# Topsheet.net
KiCad netlist of a schematic drawn in Altium Designer
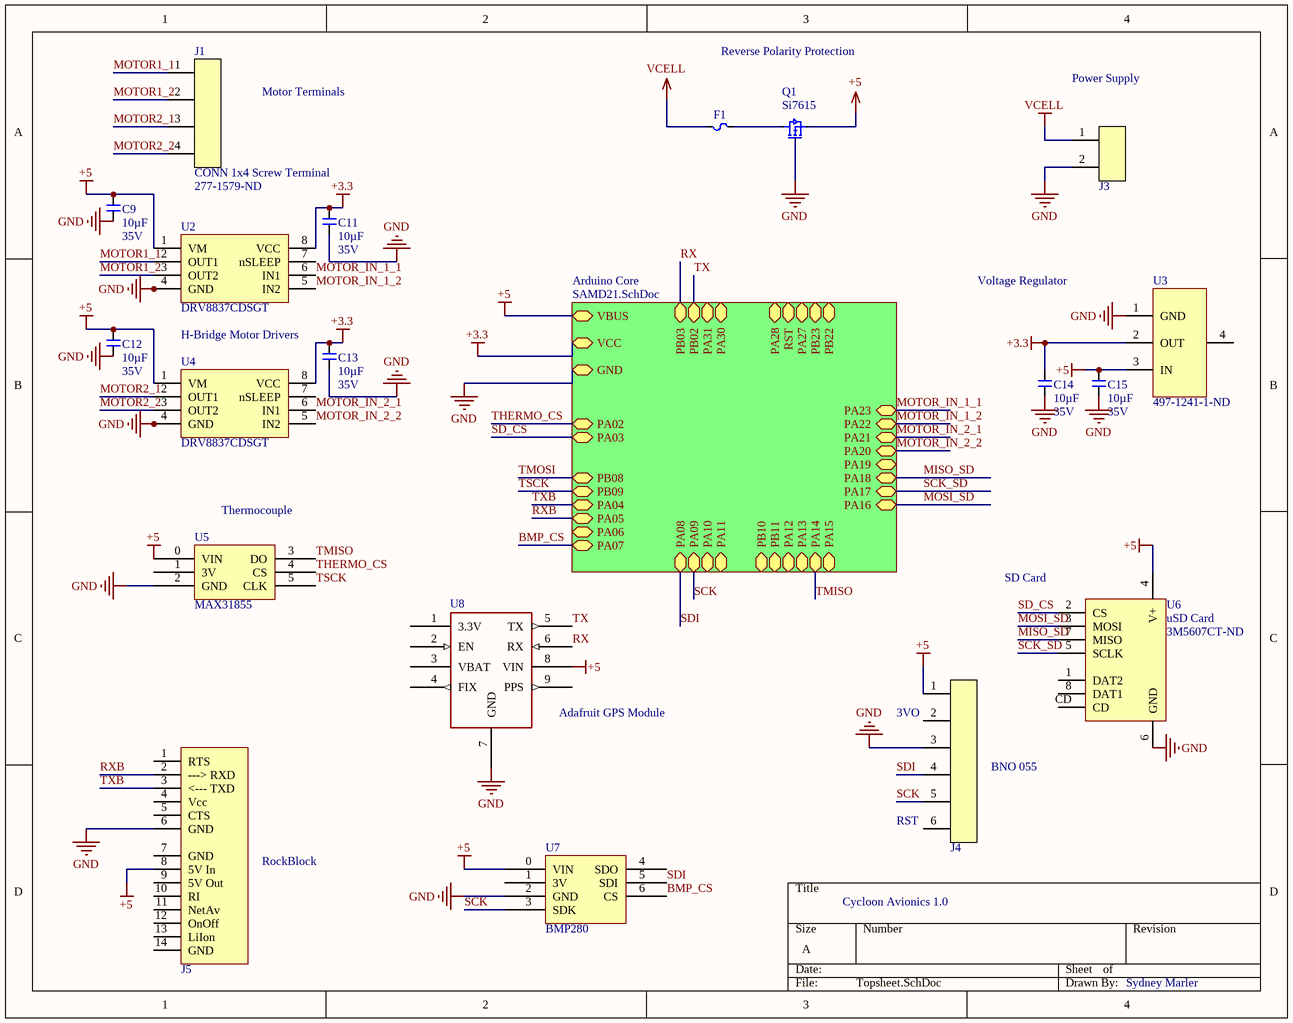
[diagram p0: Topsheet.SchDoc]

(export (version "E")
  (design (tool "Eeschema 10.0.6"))
  (components
    (comp (ref "C9")
      (value "__template_cap")
      (footprint "C0603")
      (description "CAP CER 10UF 35V X5R 0603 20%")
      (fields
        (field (name "CAPACITANCE (SHORTHAND)") "10µF")
        (field (name "RATED VOLTAGE") "35V")
        (field (name "MANUFACTURER") "Murata Electronics North America")
      )
      (libsource (lib "passives") (part "__template_cap"))
    )
    (comp (ref "C11")
      (value "__template_cap")
      (footprint "C0603")
      (description "CAP CER 10UF 35V X5R 0603 20%")
      (fields
        (field (name "CAPACITANCE (SHORTHAND)") "10µF")
        (field (name "RATED VOLTAGE") "35V")
        (field (name "MANUFACTURER") "Murata Electronics North America")
      )
      (libsource (lib "passives") (part "__template_cap"))
    )
    (comp (ref "C12")
      (value "__template_cap")
      (footprint "C0603")
      (description "CAP CER 10UF 35V X5R 0603 20%")
      (fields
        (field (name "CAPACITANCE (SHORTHAND)") "10µF")
        (field (name "RATED VOLTAGE") "35V")
        (field (name "MANUFACTURER") "Murata Electronics North America")
      )
      (libsource (lib "passives") (part "__template_cap"))
    )
    (comp (ref "C13")
      (value "__template_cap")
      (footprint "C0603")
      (description "CAP CER 10UF 35V X5R 0603 20%")
      (fields
        (field (name "CAPACITANCE (SHORTHAND)") "10µF")
        (field (name "RATED VOLTAGE") "35V")
        (field (name "MANUFACTURER") "Murata Electronics North America")
      )
      (libsource (lib "passives") (part "__template_cap"))
    )
    (comp (ref "C14")
      (value "__template_cap")
      (footprint "C0603")
      (description "CAP CER 10UF 35V X5R 0603 20%")
      (fields
        (field (name "CAPACITANCE (SHORTHAND)") "10µF")
        (field (name "RATED VOLTAGE") "35V")
        (field (name "MANUFACTURER") "Murata Electronics North America")
      )
      (libsource (lib "passives") (part "__template_cap"))
    )
    (comp (ref "C15")
      (value "__template_cap")
      (footprint "C0603")
      (description "CAP CER 10UF 35V X5R 0603 20%")
      (fields
        (field (name "CAPACITANCE (SHORTHAND)") "10µF")
        (field (name "RATED VOLTAGE") "35V")
        (field (name "MANUFACTURER") "Murata Electronics North America")
      )
      (libsource (lib "passives") (part "__template_cap"))
    )
    (comp (ref "F1") (value "__template_fuse") (libsource (lib "SSI") (part "__template_fuse")))
    (comp (ref "J1")
      (value "CONN 1x4 Screw Terminal")
      (footprint "CONN_1x4_5mm")
      (description "CONN 1x4 Screw Terminal: Phoenix Contact 1935187")
      (fields (field (name "SUPPLIER PART NUMBER 1") "277-1579-ND"))
      (libsource (lib "SSI") (part "CONN_1x4_PhoenixContact_1935187"))
    )
    (comp (ref "J3")
      (value "CONN HEADER 2POS VERT T/H")
      (footprint "CONN_1x2_100MIL")
      (fields (field (name "MANUFACTURER") "FCI") (field (name "MANUFACTURER PART NUMBER") "77311-118-02LF"))
      (libsource (lib "SSI") (part "CONN_1x2"))
    )
    (comp (ref "J4")
      (value "CONN HEADER 6POS T/H")
      (footprint "CONN_1x6_100MIL")
      (libsource (lib "SSI") (part "CONN_1x6"))
    )
    (comp (ref "J5")
      (value "ROCKBLOCK_V2")
      (footprint "ROCKBLOCK_V2")
      (description "CHILD OF SATAN, SOURCE OF BOTH TREMENDOUS FORTUNE AND UNSPEAKABLE ANGUISH")
      (libsource (lib "SSI") (part "ROCKBLOCK_V2"))
    )
    (comp (ref "Q1")
      (value "Si7615")
      (footprint "POWERPAK_1212-8_SINGLE")
      (description "MOSFET P-CH 20V 35A PPK")
      (fields
        (field (name "MANUFACTURER") "Vishay Siliconix")
        (field (name "MANUFACTURER PART NUMBER") "SI7615ADN-T1-GE3")
      )
      (libsource (lib "SSI") (part "PFET_SI7615ADN-T1"))
    )
    (comp (ref "U2")
      (value "DRV8837CDSGT")
      (footprint "8WSON")
      (description "MOTOR DRIVER 1A")
      (fields (field (name "MANUFACTURER") "Texas Instruments"))
      (libsource (lib "SSI") (part "MOTOR_HBRIDGE_DRV8837C"))
    )
    (comp (ref "U3")
      (value "LDO_LD1117S33CTR")
      (footprint "4SOT223")
      (description "IC VOLTAGE REG 3.3V 800MA SOT223 INDUSTRIAL TEMP")
      (fields
        (field (name "MANUFACTURER") "STMicroelectronics")
        (field (name "MANUFACTURER PART NUMBER") "LD1117S33CTR")
        (field (name "SUPPLIER PART NUMBER 1") "497-1241-1-ND")
      )
      (libsource (lib "SSI") (part "LDO_LD1117S33CTR"))
    )
    (comp (ref "U4")
      (value "DRV8837CDSGT")
      (footprint "8WSON")
      (description "MOTOR DRIVER 1A")
      (fields (field (name "MANUFACTURER") "Texas Instruments"))
      (libsource (lib "SSI") (part "MOTOR_HBRIDGE_DRV8837C"))
    )
    (comp (ref "U5")
      (value "MAX31855")
      (footprint "ADAFRUIT_THERMOCOUPLE_BREAKOUT")
      (libsource (lib "SSI") (part "ADAFRUIT_THERMOCOUPLE_BREAKOUT"))
    )
    (comp (ref "U6")
      (value "uSD Card")
      (footprint "MICROSD_CARD_SOCKET")
      (description "MICROSD CARD HOLDER, PUSH-PUSH")
      (fields
        (field (name "MANUFACTURER") "3M")
        (field (name "MANUFACTURER PART NUMBER") "2908-05WB-MG")
        (field (name "SUPPLIER PART NUMBER 1") "3M5607CT-ND")
      )
      (libsource (lib "SSI") (part "MICRO_SD_CARD_HOLDER"))
    )
    (comp (ref "U7")
      (value "BMP280")
      (footprint "ADAFRUIT_BMP280_BREAKOUT")
      (libsource (lib "SSI") (part "ADAFRUIT_BMP280_BREAKOUT"))
    )
    (comp (ref "U8")
      (value "Adafruit GPS Module")
      (footprint "adafruit_gps_746")
      (description "https://www.adafruit.com/product/746")
      (libsource (lib "modules") (part "ADAFRUIT_GPS_746"))
    )
  )
  (nets
    (net (code "1") (name "+3.3") (class "Default")
      (node (ref "C11") (pin "1") (pintype "passive"))
      (node (ref "C13") (pin "1") (pintype "passive"))
      (node (ref "C14") (pin "1") (pintype "passive"))
      (node (ref "U2") (pin "8") (pinfunction "VCC_8") (pintype "passive"))
      (node (ref "U3") (pin "2") (pinfunction "OUT_2") (pintype "passive"))
      (node (ref "U4") (pin "8") (pinfunction "VCC_8") (pintype "passive"))
    )
    (net (code "2") (name "+5") (class "Default")
      (node (ref "C12") (pin "1") (pintype "passive"))
      (node (ref "C15") (pin "1") (pintype "passive"))
      (node (ref "C9") (pin "1") (pintype "passive"))
      (node (ref "J4") (pin "1") (pinfunction "1_1") (pintype "passive"))
      (node (ref "J5") (pin "8") (pinfunction "5V_In_8") (pintype "passive"))
      (node (ref "Q1") (pin "2") (pintype "passive"))
      (node (ref "U2") (pin "1") (pinfunction "VM_1") (pintype "passive"))
      (node (ref "U3") (pin "3") (pinfunction "IN_3") (pintype "passive"))
      (node (ref "U4") (pin "1") (pinfunction "VM_1") (pintype "passive"))
      (node (ref "U5") (pin "0") (pinfunction "VIN_0") (pintype "passive"))
      (node (ref "U6") (pin "4") (pinfunction "V+_4") (pintype "passive"))
      (node (ref "U7") (pin "0") (pinfunction "VIN_0") (pintype "passive"))
      (node (ref "U8") (pin "8") (pinfunction "VIN_8") (pintype "power_in"))
    )
    (net (code "3") (name "/BMP_CS") (class "Default")
      (node (ref "U7") (pin "6") (pinfunction "CS_6") (pintype "passive"))
    )
    (net (code "4") (name "/MISO_SD") (class "Default")
      (node (ref "U6") (pin "7") (pinfunction "MISO_7") (pintype "passive"))
    )
    (net (code "5") (name "/MOSI_SD") (class "Default")
      (node (ref "U6") (pin "3") (pinfunction "MOSI_3") (pintype "passive"))
    )
    (net (code "6") (name "/MOTOR1_1") (class "Default")
      (node (ref "J1") (pin "1") (pinfunction "1_1") (pintype "passive"))
      (node (ref "U2") (pin "2") (pinfunction "OUT1_2") (pintype "passive"))
    )
    (net (code "7") (name "/MOTOR1_2") (class "Default")
      (node (ref "J1") (pin "2") (pinfunction "2_2") (pintype "passive"))
      (node (ref "U2") (pin "3") (pinfunction "OUT2_3") (pintype "passive"))
    )
    (net (code "8") (name "/MOTOR2_1") (class "Default")
      (node (ref "J1") (pin "3") (pinfunction "3_3") (pintype "passive"))
      (node (ref "U4") (pin "2") (pinfunction "OUT1_2") (pintype "passive"))
    )
    (net (code "9") (name "/MOTOR2_2") (class "Default")
      (node (ref "J1") (pin "4") (pinfunction "4_4") (pintype "passive"))
      (node (ref "U4") (pin "3") (pinfunction "OUT2_3") (pintype "passive"))
    )
    (net (code "10") (name "/MOTOR_IN_1_1") (class "Default")
      (node (ref "U2") (pin "6") (pinfunction "IN1_6") (pintype "passive"))
    )
    (net (code "11") (name "/MOTOR_IN_1_2") (class "Default")
      (node (ref "U2") (pin "5") (pinfunction "IN2_5") (pintype "passive"))
    )
    (net (code "12") (name "/MOTOR_IN_2_1") (class "Default")
      (node (ref "U4") (pin "6") (pinfunction "IN1_6") (pintype "passive"))
    )
    (net (code "13") (name "/MOTOR_IN_2_2") (class "Default")
      (node (ref "U4") (pin "5") (pinfunction "IN2_5") (pintype "passive"))
    )
    (net (code "30") (name "/RX") (class "Default")
      (node (ref "U8") (pin "6") (pinfunction "RX_6") (pintype "input"))
    )
    (net (code "31") (name "/RXB") (class "Default")
      (node (ref "J5") (pin "2") (pinfunction "--->_RXD_2") (pintype "passive"))
    )
    (net (code "32") (name "/SCK") (class "Default")
      (node (ref "J4") (pin "5") (pinfunction "5_5") (pintype "passive"))
      (node (ref "U7") (pin "3") (pinfunction "SDK_3") (pintype "passive"))
    )
    (net (code "33") (name "/SCK_SD") (class "Default")
      (node (ref "U6") (pin "5") (pinfunction "SCLK_5") (pintype "passive"))
    )
    (net (code "34") (name "/SDI") (class "Default")
      (node (ref "J4") (pin "4") (pinfunction "4_4") (pintype "passive"))
      (node (ref "U7") (pin "5") (pinfunction "SDI_5") (pintype "passive"))
    )
    (net (code "35") (name "/SD_CS") (class "Default")
      (node (ref "U6") (pin "2") (pinfunction "CS_2") (pintype "passive"))
    )
    (net (code "36") (name "/THERMO_CS") (class "Default")
      (node (ref "U5") (pin "4") (pinfunction "CS_4") (pintype "passive"))
    )
    (net (code "37") (name "/TMISO") (class "Default")
      (node (ref "U5") (pin "3") (pinfunction "DO_3") (pintype "passive"))
    )
    (net (code "39") (name "/TSCK") (class "Default")
      (node (ref "U5") (pin "5") (pinfunction "CLK_5") (pintype "passive"))
    )
    (net (code "40") (name "/TX") (class "Default")
      (node (ref "U8") (pin "5") (pinfunction "TX_5") (pintype "output"))
    )
    (net (code "41") (name "/TXB") (class "Default")
      (node (ref "J5") (pin "3") (pinfunction "<---_TXD_3") (pintype "passive"))
    )
    (net (code "42") (name "GND") (class "Default")
      (node (ref "C11") (pin "2") (pintype "passive"))
      (node (ref "C12") (pin "2") (pintype "passive"))
      (node (ref "C13") (pin "2") (pintype "passive"))
      (node (ref "C14") (pin "2") (pintype "passive"))
      (node (ref "C15") (pin "2") (pintype "passive"))
      (node (ref "C9") (pin "2") (pintype "passive"))
      (node (ref "J3") (pin "2") (pinfunction "2_2") (pintype "passive"))
      (node (ref "J4") (pin "3") (pinfunction "3_3") (pintype "passive"))
      (node (ref "J5") (pin "6") (pinfunction "GND_6") (pintype "passive"))
      (node (ref "Q1") (pin "1") (pintype "passive"))
      (node (ref "U2") (pin "4") (pinfunction "GND_4") (pintype "passive"))
      (node (ref "U2") (pin "PAD") (pinfunction "PAD_PAD") (pintype "passive"))
      (node (ref "U3") (pin "1") (pinfunction "GND_1") (pintype "passive"))
      (node (ref "U4") (pin "4") (pinfunction "GND_4") (pintype "passive"))
      (node (ref "U4") (pin "PAD") (pinfunction "PAD_PAD") (pintype "passive"))
      (node (ref "U5") (pin "2") (pinfunction "GND_2") (pintype "passive"))
      (node (ref "U6") (pin "6") (pinfunction "GND_6") (pintype "passive"))
      (node (ref "U7") (pin "2") (pinfunction "GND_2") (pintype "passive"))
      (node (ref "U8") (pin "7") (pinfunction "GND_7") (pintype "power_in"))
    )
    (net (code "43") (name "Net-(F1-Pad2)") (class "Default")
      (node (ref "F1") (pin "2") (pintype "passive"))
      (node (ref "Q1") (pin "3") (pintype "passive"))
    )
    (net (code "44") (name "VCELL") (class "Default")
      (node (ref "F1") (pin "1") (pintype "passive"))
      (node (ref "J3") (pin "1") (pinfunction "1_1") (pintype "passive"))
    )
    (net (code "45") (name "unconnected-(J4-Pad2)") (class "Default")
      (node (ref "J4") (pin "2") (pinfunction "2_2") (pintype "passive"))
    )
    (net (code "46") (name "unconnected-(J4-Pad6)") (class "Default")
      (node (ref "J4") (pin "6") (pinfunction "6_6") (pintype "passive"))
    )
    (net (code "47") (name "unconnected-(J5-5V_Out-Pad9)") (class "Default")
      (node (ref "J5") (pin "9") (pinfunction "5V_Out_9") (pintype "passive"))
    )
    (net (code "48") (name "unconnected-(J5-CTS-Pad5)") (class "Default")
      (node (ref "J5") (pin "5") (pinfunction "CTS_5") (pintype "passive"))
    )
    (net (code "49") (name "unconnected-(J5-GND-Pad7)") (class "Default")
      (node (ref "J5") (pin "7") (pinfunction "GND_7") (pintype "passive"))
    )
    (net (code "50") (name "unconnected-(J5-GND-Pad14)") (class "Default")
      (node (ref "J5") (pin "14") (pinfunction "GND_14") (pintype "passive"))
    )
    (net (code "51") (name "unconnected-(J5-LiIon-Pad13)") (class "Default")
      (node (ref "J5") (pin "13") (pinfunction "LiIon_13") (pintype "passive"))
    )
    (net (code "52") (name "unconnected-(J5-NetAv-Pad11)") (class "Default")
      (node (ref "J5") (pin "11") (pinfunction "NetAv_11") (pintype "passive"))
    )
    (net (code "53") (name "unconnected-(J5-OnOff-Pad12)") (class "Default")
      (node (ref "J5") (pin "12") (pinfunction "OnOff_12") (pintype "passive"))
    )
    (net (code "54") (name "unconnected-(J5-RI-Pad10)") (class "Default")
      (node (ref "J5") (pin "10") (pinfunction "RI_10") (pintype "passive"))
    )
    (net (code "55") (name "unconnected-(J5-RTS-Pad1)") (class "Default")
      (node (ref "J5") (pin "1") (pinfunction "RTS_1") (pintype "passive"))
    )
    (net (code "56") (name "unconnected-(J5-Vcc-Pad4)") (class "Default")
      (node (ref "J5") (pin "4") (pinfunction "Vcc_4") (pintype "passive"))
    )
    (net (code "57") (name "unconnected-(U2-nSLEEP-Pad7)") (class "Default")
      (node (ref "U2") (pin "7") (pinfunction "nSLEEP_7") (pintype "passive"))
    )
    (net (code "58") (name "unconnected-(U3-GND-Pad4)") (class "Default")
      (node (ref "U3") (pin "4") (pinfunction "GND_4") (pintype "passive"))
    )
    (net (code "59") (name "unconnected-(U4-nSLEEP-Pad7)") (class "Default")
      (node (ref "U4") (pin "7") (pinfunction "nSLEEP_7") (pintype "passive"))
    )
    (net (code "60") (name "unconnected-(U5-3V-Pad1)") (class "Default")
      (node (ref "U5") (pin "1") (pinfunction "3V_1") (pintype "passive"))
    )
    (net (code "61") (name "unconnected-(U6-DAT1-Pad8)") (class "Default")
      (node (ref "U6") (pin "8") (pinfunction "DAT1_8") (pintype "passive"))
    )
    (net (code "62") (name "unconnected-(U6-DAT2-Pad1)") (class "Default")
      (node (ref "U6") (pin "1") (pinfunction "DAT2_1") (pintype "passive"))
    )
    (net (code "63") (name "unconnected-(U6-PadCD)") (class "Default")
      (node (ref "U6") (pin "CD") (pinfunction "CD_CD") (pintype "passive"))
    )
    (net (code "64") (name "unconnected-(U7-3V-Pad1)") (class "Default")
      (node (ref "U7") (pin "1") (pinfunction "3V_1") (pintype "passive"))
    )
    (net (code "65") (name "unconnected-(U7-SDO-Pad4)") (class "Default")
      (node (ref "U7") (pin "4") (pinfunction "SDO_4") (pintype "passive"))
    )
    (net (code "66") (name "unconnected-(U8-3.3V-Pad1)") (class "Default")
      (node (ref "U8") (pin "1") (pinfunction "3.3V_1") (pintype "power_in"))
    )
    (net (code "67") (name "unconnected-(U8-EN-Pad2)") (class "Default")
      (node (ref "U8") (pin "2") (pinfunction "EN_2") (pintype "input"))
    )
    (net (code "68") (name "unconnected-(U8-FIX-Pad4)") (class "Default")
      (node (ref "U8") (pin "4") (pinfunction "FIX_4") (pintype "output"))
    )
    (net (code "69") (name "unconnected-(U8-PPS-Pad9)") (class "Default")
      (node (ref "U8") (pin "9") (pinfunction "PPS_9") (pintype "output"))
    )
    (net (code "70") (name "unconnected-(U8-VBAT-Pad3)") (class "Default")
      (node (ref "U8") (pin "3") (pinfunction "VBAT_3") (pintype "power_in"))
    )
  )
)
